# 07-PowerManagement.net
KiCad netlist of a schematic drawn in Altium Designer
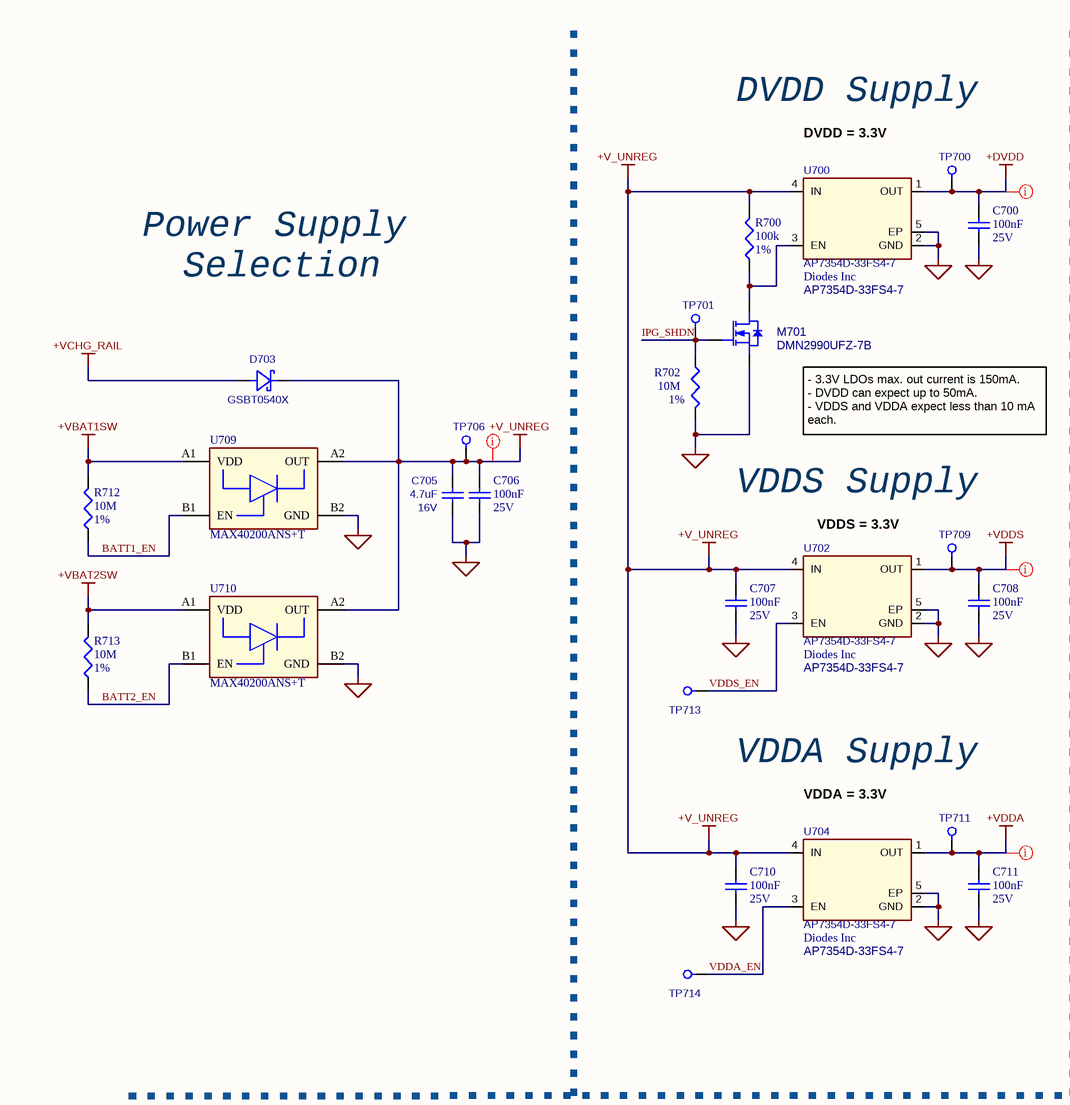
[diagram p0: 07-PowerManagement.SchDoc, left]
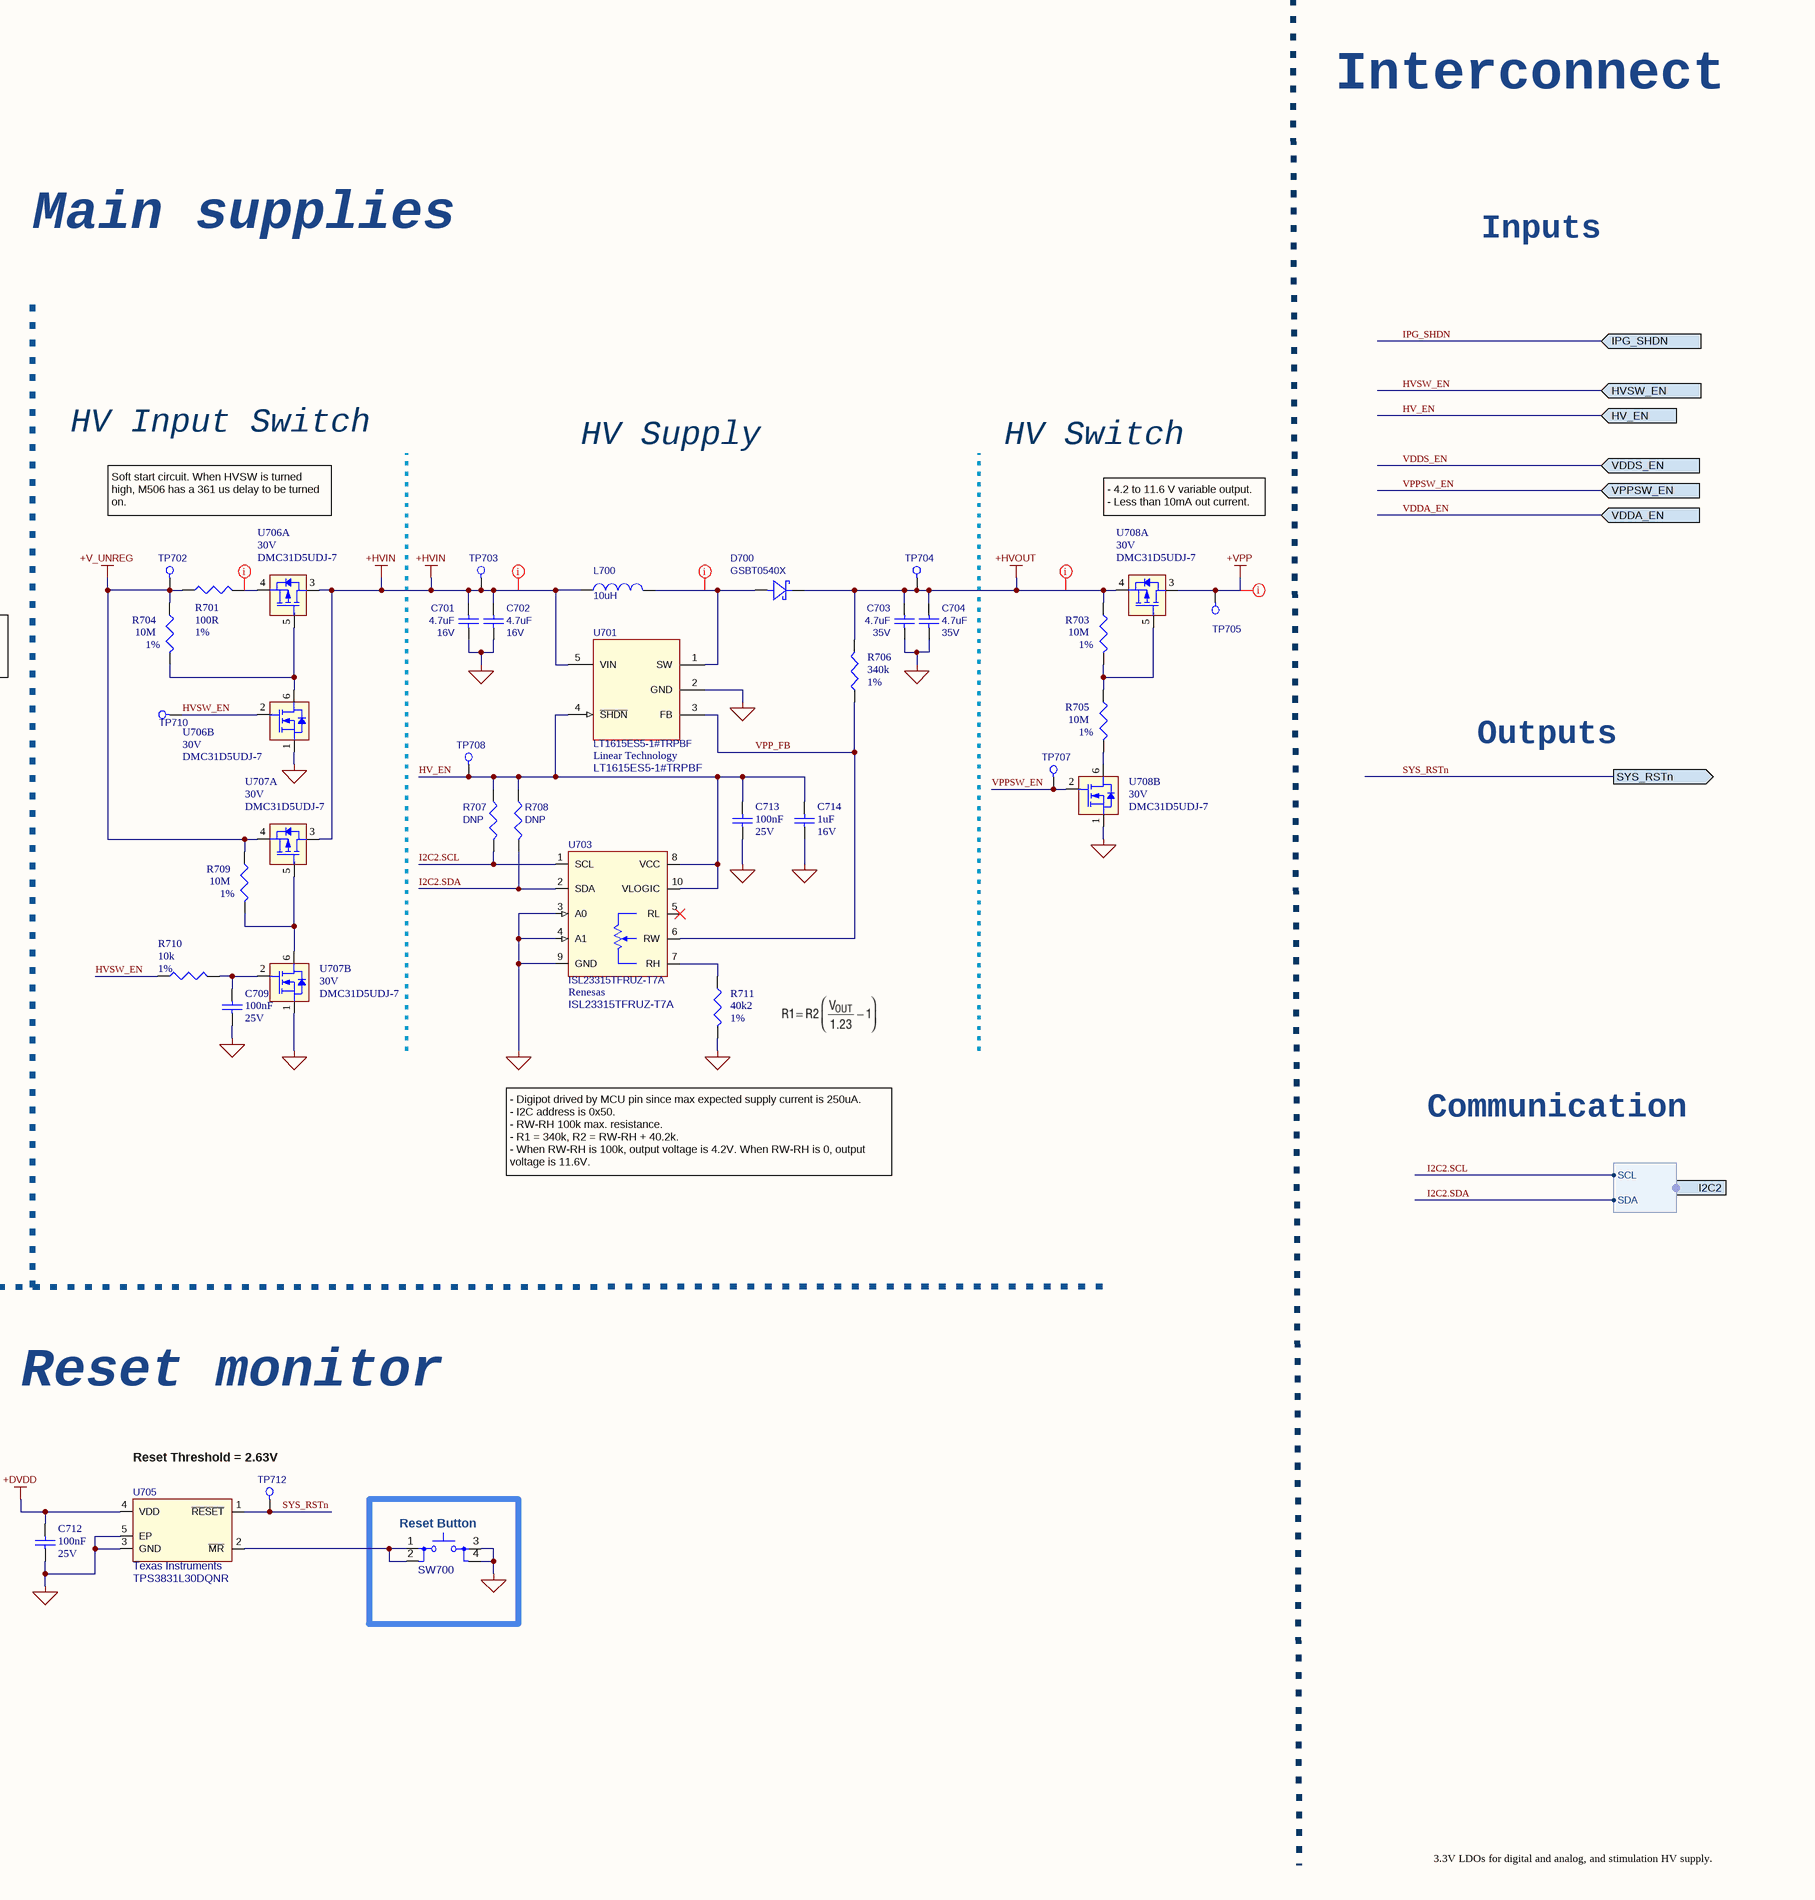
[diagram p1: 07-PowerManagement.SchDoc, right]

(export (version "E")
  (design (tool "Eeschema 10.0.6"))
  (components
    (comp (ref "C700")
      (value "100nF")
      (footprint "C0201_C")
      (fields
        (field (name "MANUFACTURER") "Murata")
        (field (name "MANUFACTURER PART NUMBER") "GRM033R61E104KE14J")
        (field (name "RATED DC VOLTAGE (URDC)") "25V")
      )
      (libsource (lib "MP-LIBRARY") (part "GRM033R61E104KE14J"))
    )
    (comp (ref "C701")
      (value "4.7uF")
      (footprint "CAP0603_REDUCED")
      (description "Capacitor, 4.7uF, X5R, 16V, 10%, 0603, Implant-grade")
      (fields
        (field (name "MANUFACTURER") "Murata")
        (field (name "RATING") "16V")
        (field (name "MANUFACTURER PART NUMBER") "GRM188R61C475KE11")
      )
      (libsource (lib "MP-LIBRARY") (part "GRM188R61C475KE11"))
    )
    (comp (ref "C702")
      (value "4.7uF")
      (footprint "CAP0603_REDUCED")
      (description "Capacitor, 4.7uF, X5R, 16V, 10%, 0603, Implant-grade")
      (fields
        (field (name "MANUFACTURER") "Murata")
        (field (name "RATING") "16V")
        (field (name "MANUFACTURER PART NUMBER") "GRM188R61C475KE11")
      )
      (libsource (lib "MP-LIBRARY") (part "GRM188R61C475KE11"))
    )
    (comp (ref "C703")
      (value "4.7uF")
      (footprint "CAP0805_REDUCED")
      (description "Capacitor, 4.7uF, X7S, 35V, 10%, 0805, Implant-grade")
      (fields
        (field (name "MANUFACTURER") "Murata")
        (field (name "RATING") "35V")
        (field (name "MANUFACTURER PART NUMBER") "GCM21BC7YA475KE36L")
      )
      (libsource (lib "MP-LIBRARY") (part "GCM21BC7YA475KE36L"))
    )
    (comp (ref "C704")
      (value "4.7uF")
      (footprint "CAP0805_REDUCED")
      (description "Capacitor, 4.7uF, X7S, 35V, 10%, 0805, Implant-grade")
      (fields
        (field (name "MANUFACTURER") "Murata")
        (field (name "RATING") "35V")
        (field (name "MANUFACTURER PART NUMBER") "GCM21BC7YA475KE36L")
      )
      (libsource (lib "MP-LIBRARY") (part "GCM21BC7YA475KE36L"))
    )
    (comp (ref "C705")
      (value "4.7uF")
      (footprint "CAP0603_REDUCED")
      (description "Capacitor, 4.7uF, X5R, 16V, 10%, 0603, Implant-grade")
      (fields
        (field (name "MANUFACTURER") "Murata")
        (field (name "RATING") "16V")
        (field (name "MANUFACTURER PART NUMBER") "GRM188R61C475KE11")
      )
      (libsource (lib "MP-LIBRARY") (part "GRM188R61C475KE11"))
    )
    (comp (ref "C706")
      (value "100nF")
      (footprint "C0201_C")
      (fields
        (field (name "MANUFACTURER") "Murata")
        (field (name "MANUFACTURER PART NUMBER") "GRM033R61E104KE14J")
        (field (name "RATED DC VOLTAGE (URDC)") "25V")
      )
      (libsource (lib "MP-LIBRARY") (part "GRM033R61E104KE14J"))
    )
    (comp (ref "C707")
      (value "100nF")
      (footprint "C0201_C")
      (fields
        (field (name "MANUFACTURER") "Murata")
        (field (name "MANUFACTURER PART NUMBER") "GRM033R61E104KE14J")
        (field (name "RATED DC VOLTAGE (URDC)") "25V")
      )
      (libsource (lib "MP-LIBRARY") (part "GRM033R61E104KE14J"))
    )
    (comp (ref "C708")
      (value "100nF")
      (footprint "C0201_C")
      (fields
        (field (name "MANUFACTURER") "Murata")
        (field (name "MANUFACTURER PART NUMBER") "GRM033R61E104KE14J")
        (field (name "RATED DC VOLTAGE (URDC)") "25V")
      )
      (libsource (lib "MP-LIBRARY") (part "GRM033R61E104KE14J"))
    )
    (comp (ref "C709")
      (value "100nF")
      (footprint "C0201_C")
      (fields
        (field (name "MANUFACTURER") "Murata")
        (field (name "MANUFACTURER PART NUMBER") "GRM033R61E104KE14J")
        (field (name "RATED DC VOLTAGE (URDC)") "25V")
      )
      (libsource (lib "MP-LIBRARY") (part "GRM033R61E104KE14J"))
    )
    (comp (ref "C710")
      (value "100nF")
      (footprint "C0201_C")
      (fields
        (field (name "MANUFACTURER") "Murata")
        (field (name "MANUFACTURER PART NUMBER") "GRM033R61E104KE14J")
        (field (name "RATED DC VOLTAGE (URDC)") "25V")
      )
      (libsource (lib "MP-LIBRARY") (part "GRM033R61E104KE14J"))
    )
    (comp (ref "C711")
      (value "100nF")
      (footprint "C0201_C")
      (fields
        (field (name "MANUFACTURER") "Murata")
        (field (name "MANUFACTURER PART NUMBER") "GRM033R61E104KE14J")
        (field (name "RATED DC VOLTAGE (URDC)") "25V")
      )
      (libsource (lib "MP-LIBRARY") (part "GRM033R61E104KE14J"))
    )
    (comp (ref "C712")
      (value "100nF")
      (footprint "C0201_C")
      (fields
        (field (name "MANUFACTURER") "Murata")
        (field (name "MANUFACTURER PART NUMBER") "GRM033R61E104KE14J")
        (field (name "RATED DC VOLTAGE (URDC)") "25V")
      )
      (libsource (lib "MP-LIBRARY") (part "GRM033R61E104KE14J"))
    )
    (comp (ref "C713")
      (value "100nF")
      (footprint "C0201_C")
      (fields
        (field (name "MANUFACTURER") "Murata")
        (field (name "MANUFACTURER PART NUMBER") "GRM033R61E104KE14J")
        (field (name "RATED DC VOLTAGE (URDC)") "25V")
      )
      (libsource (lib "MP-LIBRARY") (part "GRM033R61E104KE14J"))
    )
    (comp (ref "C714")
      (value "1uF")
      (footprint "C0201_C")
      (fields
        (field (name "MANUFACTURER") "Murata")
        (field (name "MANUFACTURER PART NUMBER") "GRM033R61C105ME15D")
        (field (name "RATED DC VOLTAGE (URDC)") "16V")
      )
      (libsource (lib "MP-LIBRARY") (part "GRM033R61C105ME15D"))
    )
    (comp (ref "D700")
      (value "GSBT0540X")
      (footprint "STM_SOD-523_R")
      (description "DIODE SCHOTTKY 40V 500MA SOD523")
      (fields (field (name "MANUFACTURER") "Good-Ark Semiconductor"))
      (libsource (lib "MP-LIBRARY") (part "GSBT0540X"))
    )
    (comp (ref "D703")
      (value "GSBT0540X")
      (footprint "STM_SOD-523_R")
      (description "DIODE SCHOTTKY 40V 500MA SOD523")
      (fields (field (name "MANUFACTURER") "Good-Ark Semiconductor"))
      (libsource (lib "MP-LIBRARY") (part "GSBT0540X"))
    )
    (comp (ref "L700")
      (value "10uH")
      (footprint "WURTH_74438323100_REDUCED")
      (description "Inductor, 10uH, 600mA, 20%, 1008")
      (fields (field (name "MANUFACTURER") "Wurth") (field (name "MANUFACTURER PART NUMBER") "74438323100"))
      (libsource (lib "MP-LIBRARY") (part "74438323100"))
    )
    (comp (ref "M701")
      (value "DMN2990UFZ-7B")
      (footprint "DIODESINC_X2-DFN0606-3")
      (description "MOSFET, N-Chan, 20V, 170mA, DFN0606")
      (fields (field (name "MANUFACTURER") "Diodes Inc"))
      (libsource (lib "MP-LIBRARY") (part "DMN2990UFZ-7B"))
    )
    (comp (ref "R700")
      (value "100k")
      (footprint "R0201_C")
      (fields
        (field (name "MANUFACTURER") "Vishay")
        (field (name "MANUFACTURER PART NUMBER") "CRCW0201100KFNED")
        (field (name "TOLERANCE") "1%")
        (field (name "POWER") "50mW")
      )
      (libsource (lib "MP-LIBRARY") (part "CRCW0201100KFNED"))
    )
    (comp (ref "R701")
      (value "100R")
      (footprint "R0201_C")
      (fields
        (field (name "MANUFACTURER") "Vishay")
        (field (name "MANUFACTURER PART NUMBER") "CRCW0201100RFNED")
        (field (name "TOLERANCE") "1%")
        (field (name "POWER") "50mW")
      )
      (libsource (lib "MP-LIBRARY") (part "CRCW0201100RFNED"))
    )
    (comp (ref "R702")
      (value "10M")
      (footprint "R0201_C")
      (fields
        (field (name "MANUFACTURER") "Vishay Draloric")
        (field (name "MANUFACTURER PART NUMBER") "CRCW020110M0FNED")
        (field (name "TOLERANCE") "1%")
        (field (name "POWER") "50mW")
      )
      (libsource (lib "MP-LIBRARY") (part "CRCW020110M0FNED"))
    )
    (comp (ref "R703")
      (value "10M")
      (footprint "R0201_C")
      (fields
        (field (name "MANUFACTURER") "Vishay Draloric")
        (field (name "MANUFACTURER PART NUMBER") "CRCW020110M0FNED")
        (field (name "TOLERANCE") "1%")
        (field (name "POWER") "50mW")
      )
      (libsource (lib "MP-LIBRARY") (part "CRCW020110M0FNED"))
    )
    (comp (ref "R704")
      (value "10M")
      (footprint "R0201_C")
      (fields
        (field (name "MANUFACTURER") "Vishay Draloric")
        (field (name "MANUFACTURER PART NUMBER") "CRCW020110M0FNED")
        (field (name "TOLERANCE") "1%")
        (field (name "POWER") "50mW")
      )
      (libsource (lib "MP-LIBRARY") (part "CRCW020110M0FNED"))
    )
    (comp (ref "R705")
      (value "10M")
      (footprint "R0201_C")
      (fields
        (field (name "MANUFACTURER") "Vishay Draloric")
        (field (name "MANUFACTURER PART NUMBER") "CRCW020110M0FNED")
        (field (name "TOLERANCE") "1%")
        (field (name "POWER") "50mW")
      )
      (libsource (lib "MP-LIBRARY") (part "CRCW020110M0FNED"))
    )
    (comp (ref "R706")
      (value "340k")
      (footprint "R0201_C")
      (fields
        (field (name "MANUFACTURER") "Vishay")
        (field (name "MANUFACTURER PART NUMBER") "CRCW0201340KFKED")
        (field (name "TOLERANCE") "1%")
        (field (name "POWER") "50mW")
      )
      (libsource (lib "MP-LIBRARY") (part "CRCW0201340KFKED"))
    )
    (comp (ref "R707")
      (value "DNP")
      (footprint "RES0402_REDUCED")
      (description "Resistor, DNP, 0402")
      (libsource (lib "MP-LIBRARY") (part "RES_DNP_0402"))
    )
    (comp (ref "R708")
      (value "DNP")
      (footprint "RES0402_REDUCED")
      (description "Resistor, DNP, 0402")
      (libsource (lib "MP-LIBRARY") (part "RES_DNP_0402"))
    )
    (comp (ref "R709")
      (value "10M")
      (footprint "R0201_C")
      (fields
        (field (name "MANUFACTURER") "Vishay Draloric")
        (field (name "MANUFACTURER PART NUMBER") "CRCW020110M0FNED")
        (field (name "TOLERANCE") "1%")
        (field (name "POWER") "50mW")
      )
      (libsource (lib "MP-LIBRARY") (part "CRCW020110M0FNED"))
    )
    (comp (ref "R710")
      (value "10k")
      (footprint "R0201_C")
      (fields
        (field (name "MANUFACTURER") "Vishay")
        (field (name "MANUFACTURER PART NUMBER") "CRCW020110K0FNED")
        (field (name "TOLERANCE") "1%")
        (field (name "POWER") "50mW")
      )
      (libsource (lib "MP-LIBRARY") (part "CRCW020110K0FNED"))
    )
    (comp (ref "R711")
      (value "40k2")
      (footprint "R0201_C")
      (fields
        (field (name "MANUFACTURER") "Vishay")
        (field (name "MANUFACTURER PART NUMBER") "CRCW020140K2FNED")
        (field (name "TOLERANCE") "1%")
        (field (name "POWER") "50mW")
      )
      (libsource (lib "MP-LIBRARY") (part "CRCW020140K2FNED"))
    )
    (comp (ref "R712")
      (value "10M")
      (footprint "R0201_C")
      (fields
        (field (name "MANUFACTURER") "Vishay Draloric")
        (field (name "MANUFACTURER PART NUMBER") "CRCW020110M0FNED")
        (field (name "TOLERANCE") "1%")
        (field (name "POWER") "50mW")
      )
      (libsource (lib "MP-LIBRARY") (part "CRCW020110M0FNED"))
    )
    (comp (ref "R713")
      (value "10M")
      (footprint "R0201_C")
      (fields
        (field (name "MANUFACTURER") "Vishay Draloric")
        (field (name "MANUFACTURER PART NUMBER") "CRCW020110M0FNED")
        (field (name "TOLERANCE") "1%")
        (field (name "POWER") "50mW")
      )
      (libsource (lib "MP-LIBRARY") (part "CRCW020110M0FNED"))
    )
    (comp (ref "SW700")
      (value "PTS647SN50SMTR2LFS")
      (footprint "CK_PTS647")
      (description "Pushbutton, NO-MOM, 12V, 0.05A, SMT")
      (fields (field (name "MANUFACTURER") "C&K"))
      (libsource (lib "MP-LIBRARY") (part "PTS647SN50SMTR2LFS"))
    )
    (comp (ref "TP700")
      (value "Test Point")
      (footprint "testpad_0.9mm")
      (description "Test pad, 0.90mm circular pad")
      (libsource (lib "MP-LIBRARY") (part "Test Point"))
    )
    (comp (ref "TP701")
      (value "Test Point")
      (footprint "testpad_0.9mm")
      (description "Test pad, 0.90mm circular pad")
      (libsource (lib "MP-LIBRARY") (part "Test Point"))
    )
    (comp (ref "TP702")
      (value "Test Point")
      (footprint "testpad_0.9mm")
      (description "Test pad, 0.90mm circular pad")
      (libsource (lib "MP-LIBRARY") (part "Test Point"))
    )
    (comp (ref "TP703")
      (value "Test Point")
      (footprint "testpad_0.9mm")
      (description "Test pad, 0.90mm circular pad")
      (libsource (lib "MP-LIBRARY") (part "Test Point"))
    )
    (comp (ref "TP704")
      (value "Test Point")
      (footprint "testpad_0.9mm")
      (description "Test pad, 0.90mm circular pad")
      (libsource (lib "MP-LIBRARY") (part "Test Point"))
    )
    (comp (ref "TP705")
      (value "Test Point")
      (footprint "testpad_0.9mm")
      (description "Test pad, 0.90mm circular pad")
      (libsource (lib "MP-LIBRARY") (part "Test Point"))
    )
    (comp (ref "TP706")
      (value "Test Point")
      (footprint "testpad_0.9mm")
      (description "Test pad, 0.90mm circular pad")
      (libsource (lib "MP-LIBRARY") (part "Test Point"))
    )
    (comp (ref "TP707")
      (value "Test Point")
      (footprint "testpad_0.9mm")
      (description "Test pad, 0.90mm circular pad")
      (libsource (lib "MP-LIBRARY") (part "Test Point"))
    )
    (comp (ref "TP708")
      (value "Test Point")
      (footprint "testpad_0.9mm")
      (description "Test pad, 0.90mm circular pad")
      (libsource (lib "MP-LIBRARY") (part "Test Point"))
    )
    (comp (ref "TP709")
      (value "Test Point")
      (footprint "testpad_0.9mm")
      (description "Test pad, 0.90mm circular pad")
      (libsource (lib "MP-LIBRARY") (part "Test Point"))
    )
    (comp (ref "TP710")
      (value "Test Point")
      (footprint "testpad_0.9mm")
      (description "Test pad, 0.90mm circular pad")
      (libsource (lib "MP-LIBRARY") (part "Test Point"))
    )
    (comp (ref "TP711")
      (value "Test Point")
      (footprint "testpad_0.9mm")
      (description "Test pad, 0.90mm circular pad")
      (libsource (lib "MP-LIBRARY") (part "Test Point"))
    )
    (comp (ref "TP712")
      (value "Test Point")
      (footprint "testpad_0.9mm")
      (description "Test pad, 0.90mm circular pad")
      (libsource (lib "MP-LIBRARY") (part "Test Point"))
    )
    (comp (ref "TP713")
      (value "Test Point")
      (footprint "testpad_0.9mm")
      (description "Test pad, 0.90mm circular pad")
      (libsource (lib "MP-LIBRARY") (part "Test Point"))
    )
    (comp (ref "TP714")
      (value "Test Point")
      (footprint "testpad_0.9mm")
      (description "Test pad, 0.90mm circular pad")
      (libsource (lib "MP-LIBRARY") (part "Test Point"))
    )
    (comp (ref "U700")
      (value "AP7354D-33FS4-7")
      (footprint "X2-DFN1010-4 (Type B)")
      (description "LDO Regulator, 3.3V, Shutdown, DFN1010-4")
      (fields (field (name "MANUFACTURER") "Diodes Inc") (field (name "ALTIUM_VALUE") "AP7354D-33FS4-7"))
      (libsource (lib "MP-LIBRARY") (part "AP7354D-33FS4-7"))
    )
    (comp (ref "U701")
      (value "LT1615ES5-1#TRPBF")
      (footprint "LT_S5_L")
      (description "Boost, SEPIC Switching Regulator IC Positive Adjustable 1.23V 1 Output 75mA (Switch) SOT-23-5")
      (fields
        (field (name "MANUFACTURER") "Linear Technology")
        (field (name "ALTIUM_VALUE") "LT1615ES5-1#TRPBF")
      )
      (libsource (lib "MP-LIBRARY") (part "LT1615ES5-1#TRPBF"))
    )
    (comp (ref "U702")
      (value "AP7354D-33FS4-7")
      (footprint "X2-DFN1010-4 (Type B)")
      (description "LDO Regulator, 3.3V, Shutdown, DFN1010-4")
      (fields (field (name "MANUFACTURER") "Diodes Inc") (field (name "ALTIUM_VALUE") "AP7354D-33FS4-7"))
      (libsource (lib "MP-LIBRARY") (part "AP7354D-33FS4-7"))
    )
    (comp (ref "U703")
      (value "ISL23315TFRUZ-T7A")
      (footprint "RENESAS_L10.2.1X1.6A_UTQFN10")
      (description "Digital potentiometer, 256 taps, 100k, I2C, QFN-10")
      (fields (field (name "MANUFACTURER") "Renesas") (field (name "ALTIUM_VALUE") "ISL23315TFRUZ-T7A"))
      (libsource (lib "MP-LIBRARY") (part "ISL23315TFRUZ-T7A"))
    )
    (comp (ref "U704")
      (value "AP7354D-33FS4-7")
      (footprint "X2-DFN1010-4 (Type B)")
      (description "LDO Regulator, 3.3V, Shutdown, DFN1010-4")
      (fields (field (name "MANUFACTURER") "Diodes Inc") (field (name "ALTIUM_VALUE") "AP7354D-33FS4-7"))
      (libsource (lib "MP-LIBRARY") (part "AP7354D-33FS4-7"))
    )
    (comp (ref "U705")
      (value "TPS3831L30DQNR")
      (footprint "TI_X2SON_DQN0004A")
      (description "Reset Monitor, 2.63V, Active low, X2SON")
      (fields (field (name "MANUFACTURER") "Texas Instruments"))
      (libsource (lib "MP-LIBRARY") (part "TPS3831L30DQNR"))
    )
    (comp (ref "U706")
      (value "DMC31D5UDJ-7")
      (footprint "DIODESINC_SOT-963-6")
      (description "MOSFET N/P-CH 30V 0.22A SOT963")
      (fields (field (name "MANUFACTURER") "Diodes inc.") (field (name "VDS(MAX)") "30V"))
      (libsource (lib "MP-LIBRARY") (part "DMC31D5UDJ-7"))
    )
    (comp (ref "U707")
      (value "DMC31D5UDJ-7")
      (footprint "DIODESINC_SOT-963-6")
      (description "MOSFET N/P-CH 30V 0.22A SOT963")
      (fields (field (name "MANUFACTURER") "Diodes inc.") (field (name "VDS(MAX)") "30V"))
      (libsource (lib "MP-LIBRARY") (part "DMC31D5UDJ-7"))
    )
    (comp (ref "U708")
      (value "DMC31D5UDJ-7")
      (footprint "DIODESINC_SOT-963-6")
      (description "MOSFET N/P-CH 30V 0.22A SOT963")
      (fields (field (name "MANUFACTURER") "Diodes inc.") (field (name "VDS(MAX)") "30V"))
      (libsource (lib "MP-LIBRARY") (part "DMC31D5UDJ-7"))
    )
    (comp (ref "U709")
      (value "MAX40200ANS+T")
      (footprint "BGA4N35P2X2_72X72X50N")
      (description "OR Controller Source Selector Switch P-Channel 1:1 4-WLP (0.73x0.73)")
      (fields (field (name "MANUFACTURER") "Maxim Integrated"))
      (libsource (lib "MP-LIBRARY") (part "MAX40200ANS+T"))
    )
    (comp (ref "U710")
      (value "MAX40200ANS+T")
      (footprint "BGA4N35P2X2_72X72X50N")
      (description "OR Controller Source Selector Switch P-Channel 1:1 4-WLP (0.73x0.73)")
      (fields (field (name "MANUFACTURER") "Maxim Integrated"))
      (libsource (lib "MP-LIBRARY") (part "MAX40200ANS+T"))
    )
  )
  (nets
    (net (code "2") (name "+DVDD") (class "Default")
      (node (ref "C700") (pin "2") (pinfunction "2_2") (pintype "passive"))
      (node (ref "C712") (pin "2") (pinfunction "2_2") (pintype "passive"))
      (node (ref "TP700") (pin "1") (pinfunction "1_1") (pintype "passive"))
      (node (ref "U700") (pin "1") (pinfunction "OUT_1") (pintype "passive"))
      (node (ref "U705") (pin "4") (pinfunction "VDD_4") (pintype "passive"))
    )
    (net (code "3") (name "+HVIN") (class "Default")
      (node (ref "C701") (pin "1") (pinfunction "1_1") (pintype "passive"))
      (node (ref "C702") (pin "1") (pinfunction "1_1") (pintype "passive"))
      (node (ref "L700") (pin "1") (pinfunction "1_1") (pintype "passive"))
      (node (ref "TP703") (pin "1") (pinfunction "1_1") (pintype "passive"))
      (node (ref "U701") (pin "5") (pinfunction "VIN_5") (pintype "power_in"))
      (node (ref "U706") (pin "3") (pinfunction "3_3") (pintype "passive"))
      (node (ref "U707") (pin "3") (pinfunction "3_3") (pintype "passive"))
    )
    (net (code "4") (name "+HVOUT") (class "Default")
      (node (ref "C703") (pin "1") (pinfunction "1_1") (pintype "passive"))
      (node (ref "C704") (pin "1") (pinfunction "1_1") (pintype "passive"))
      (node (ref "D700") (pin "1") (pinfunction "1_1") (pintype "passive"))
      (node (ref "R703") (pin "1") (pinfunction "1_1") (pintype "passive"))
      (node (ref "R706") (pin "2") (pinfunction "2_2") (pintype "passive"))
      (node (ref "TP704") (pin "1") (pinfunction "1_1") (pintype "passive"))
      (node (ref "U708") (pin "4") (pinfunction "4_4") (pintype "passive"))
    )
    (net (code "5") (name "+VBAT1SW") (class "Default")
      (node (ref "R712") (pin "2") (pinfunction "2_2") (pintype "passive"))
      (node (ref "U709") (pin "A1") (pinfunction "VDD_A1") (pintype "passive"))
    )
    (net (code "6") (name "+VBAT2SW") (class "Default")
      (node (ref "R713") (pin "2") (pinfunction "2_2") (pintype "passive"))
      (node (ref "U710") (pin "A1") (pinfunction "VDD_A1") (pintype "passive"))
    )
    (net (code "7") (name "+VCHG_RAIL") (class "Default")
      (node (ref "D703") (pin "2") (pinfunction "2_2") (pintype "passive"))
    )
    (net (code "8") (name "+VDDA") (class "Default")
      (node (ref "C711") (pin "2") (pinfunction "2_2") (pintype "passive"))
      (node (ref "TP711") (pin "1") (pinfunction "1_1") (pintype "passive"))
      (node (ref "U704") (pin "1") (pinfunction "OUT_1") (pintype "passive"))
    )
    (net (code "9") (name "+VDDS") (class "Default")
      (node (ref "C708") (pin "2") (pinfunction "2_2") (pintype "passive"))
      (node (ref "TP709") (pin "1") (pinfunction "1_1") (pintype "passive"))
      (node (ref "U702") (pin "1") (pinfunction "OUT_1") (pintype "passive"))
    )
    (net (code "10") (name "+VPP") (class "Default")
      (node (ref "TP705") (pin "1") (pinfunction "1_1") (pintype "passive"))
      (node (ref "U708") (pin "3") (pinfunction "3_3") (pintype "passive"))
    )
    (net (code "11") (name "+V_UNREG") (class "Default")
      (node (ref "C705") (pin "1") (pinfunction "1_1") (pintype "passive"))
      (node (ref "C706") (pin "2") (pinfunction "2_2") (pintype "passive"))
      (node (ref "C707") (pin "2") (pinfunction "2_2") (pintype "passive"))
      (node (ref "C710") (pin "2") (pinfunction "2_2") (pintype "passive"))
      (node (ref "D703") (pin "1") (pinfunction "1_1") (pintype "passive"))
      (node (ref "R700") (pin "2") (pinfunction "2_2") (pintype "passive"))
      (node (ref "R701") (pin "1") (pinfunction "1_1") (pintype "passive"))
      (node (ref "R704") (pin "1") (pinfunction "1_1") (pintype "passive"))
      (node (ref "R709") (pin "1") (pinfunction "1_1") (pintype "passive"))
      (node (ref "TP702") (pin "1") (pinfunction "1_1") (pintype "passive"))
      (node (ref "TP706") (pin "1") (pinfunction "1_1") (pintype "passive"))
      (node (ref "U700") (pin "4") (pinfunction "IN_4") (pintype "passive"))
      (node (ref "U702") (pin "4") (pinfunction "IN_4") (pintype "passive"))
      (node (ref "U704") (pin "4") (pinfunction "IN_4") (pintype "passive"))
      (node (ref "U707") (pin "4") (pinfunction "4_4") (pintype "passive"))
      (node (ref "U709") (pin "A2") (pinfunction "OUT_A2") (pintype "passive"))
      (node (ref "U710") (pin "A2") (pinfunction "OUT_A2") (pintype "passive"))
    )
    (net (code "12") (name "/BATT1_EN") (class "Default")
      (node (ref "R712") (pin "1") (pinfunction "1_1") (pintype "passive"))
      (node (ref "U709") (pin "B1") (pinfunction "EN_B1") (pintype "passive"))
    )
    (net (code "13") (name "/BATT2_EN") (class "Default")
      (node (ref "R713") (pin "1") (pinfunction "1_1") (pintype "passive"))
      (node (ref "U710") (pin "B1") (pinfunction "EN_B1") (pintype "passive"))
    )
    (net (code "14") (name "/HVSW_EN") (class "Default")
      (node (ref "R710") (pin "1") (pinfunction "1_1") (pintype "passive"))
      (node (ref "TP710") (pin "1") (pinfunction "1_1") (pintype "passive"))
      (node (ref "U706") (pin "2") (pinfunction "2_2") (pintype "passive"))
    )
    (net (code "15") (name "/HV_EN") (class "Default")
      (node (ref "C713") (pin "2") (pinfunction "2_2") (pintype "passive"))
      (node (ref "C714") (pin "2") (pinfunction "2_2") (pintype "passive"))
      (node (ref "R707") (pin "1") (pinfunction "1_1") (pintype "passive"))
      (node (ref "R708") (pin "1") (pinfunction "1_1") (pintype "passive"))
      (node (ref "TP708") (pin "1") (pinfunction "1_1") (pintype "passive"))
      (node (ref "U701") (pin "4") (pinfunction "~{SHDN}_4") (pintype "input"))
      (node (ref "U703") (pin "10") (pinfunction "VLOGIC_10") (pintype "passive"))
      (node (ref "U703") (pin "8") (pinfunction "VCC_8") (pintype "passive"))
    )
    (net (code "16") (name "/I2C2.SCL") (class "Default")
      (node (ref "R707") (pin "2") (pinfunction "2_2") (pintype "passive"))
      (node (ref "U703") (pin "1") (pinfunction "SCL_1") (pintype "passive"))
    )
    (net (code "17") (name "/I2C2.SDA") (class "Default")
      (node (ref "R708") (pin "2") (pinfunction "2_2") (pintype "passive"))
      (node (ref "U703") (pin "2") (pinfunction "SDA_2") (pintype "passive"))
    )
    (net (code "18") (name "/IPG_SHDN") (class "Default")
      (node (ref "M701") (pin "1") (pinfunction "G_1") (pintype "passive"))
      (node (ref "R702") (pin "1") (pinfunction "1_1") (pintype "passive"))
      (node (ref "TP701") (pin "1") (pinfunction "1_1") (pintype "passive"))
    )
    (net (code "19") (name "/SYS_RSTn") (class "Default")
      (node (ref "TP712") (pin "1") (pinfunction "1_1") (pintype "passive"))
      (node (ref "U705") (pin "1") (pinfunction "~{RESET}_1") (pintype "passive"))
    )
    (net (code "20") (name "/VDDA_EN") (class "Default")
      (node (ref "TP714") (pin "1") (pinfunction "1_1") (pintype "passive"))
      (node (ref "U704") (pin "3") (pinfunction "EN_3") (pintype "passive"))
    )
    (net (code "21") (name "/VDDS_EN") (class "Default")
      (node (ref "TP713") (pin "1") (pinfunction "1_1") (pintype "passive"))
      (node (ref "U702") (pin "3") (pinfunction "EN_3") (pintype "passive"))
    )
    (net (code "22") (name "/VPPSW_EN") (class "Default")
      (node (ref "TP707") (pin "1") (pinfunction "1_1") (pintype "passive"))
      (node (ref "U708") (pin "2") (pinfunction "2_2") (pintype "passive"))
    )
    (net (code "23") (name "/VPP_FB") (class "Default")
      (node (ref "R706") (pin "1") (pinfunction "1_1") (pintype "passive"))
      (node (ref "U701") (pin "3") (pinfunction "FB_3") (pintype "passive"))
      (node (ref "U703") (pin "6") (pinfunction "RW_6") (pintype "passive"))
    )
    (net (code "25") (name "GND") (class "Default")
      (node (ref "C700") (pin "1") (pinfunction "1_1") (pintype "passive"))
      (node (ref "C701") (pin "2") (pinfunction "2_2") (pintype "passive"))
      (node (ref "C702") (pin "2") (pinfunction "2_2") (pintype "passive"))
      (node (ref "C703") (pin "2") (pinfunction "2_2") (pintype "passive"))
      (node (ref "C704") (pin "2") (pinfunction "2_2") (pintype "passive"))
      (node (ref "C705") (pin "2") (pinfunction "2_2") (pintype "passive"))
      (node (ref "C706") (pin "1") (pinfunction "1_1") (pintype "passive"))
      (node (ref "C707") (pin "1") (pinfunction "1_1") (pintype "passive"))
      (node (ref "C708") (pin "1") (pinfunction "1_1") (pintype "passive"))
      (node (ref "C709") (pin "1") (pinfunction "1_1") (pintype "passive"))
      (node (ref "C710") (pin "1") (pinfunction "1_1") (pintype "passive"))
      (node (ref "C711") (pin "1") (pinfunction "1_1") (pintype "passive"))
      (node (ref "C712") (pin "1") (pinfunction "1_1") (pintype "passive"))
      (node (ref "C713") (pin "1") (pinfunction "1_1") (pintype "passive"))
      (node (ref "C714") (pin "1") (pinfunction "1_1") (pintype "passive"))
      (node (ref "M701") (pin "2") (pinfunction "S_2") (pintype "passive"))
      (node (ref "R702") (pin "2") (pinfunction "2_2") (pintype "passive"))
      (node (ref "R711") (pin "2") (pinfunction "2_2") (pintype "passive"))
      (node (ref "SW700") (pin "3") (pinfunction "3_3") (pintype "passive"))
      (node (ref "SW700") (pin "4") (pinfunction "4_4") (pintype "passive"))
      (node (ref "U700") (pin "2") (pinfunction "GND_2") (pintype "power_in"))
      (node (ref "U700") (pin "5") (pinfunction "EP_5") (pintype "passive"))
      (node (ref "U701") (pin "2") (pinfunction "GND_2") (pintype "power_in"))
      (node (ref "U702") (pin "2") (pinfunction "GND_2") (pintype "power_in"))
      (node (ref "U702") (pin "5") (pinfunction "EP_5") (pintype "passive"))
      (node (ref "U703") (pin "3") (pinfunction "A0_3") (pintype "input"))
      (node (ref "U703") (pin "4") (pinfunction "A1_4") (pintype "input"))
      (node (ref "U703") (pin "9") (pinfunction "GND_9") (pintype "power_in"))
      (node (ref "U704") (pin "2") (pinfunction "GND_2") (pintype "power_in"))
      (node (ref "U704") (pin "5") (pinfunction "EP_5") (pintype "passive"))
      (node (ref "U705") (pin "3") (pinfunction "GND_3") (pintype "passive"))
      (node (ref "U705") (pin "5") (pinfunction "EP_5") (pintype "passive"))
      (node (ref "U706") (pin "1") (pinfunction "1_1") (pintype "passive"))
      (node (ref "U707") (pin "1") (pinfunction "1_1") (pintype "passive"))
      (node (ref "U708") (pin "1") (pinfunction "1_1") (pintype "passive"))
      (node (ref "U709") (pin "B2") (pinfunction "GND_B2") (pintype "passive"))
      (node (ref "U710") (pin "B2") (pinfunction "GND_B2") (pintype "passive"))
    )
    (net (code "26") (name "Net-(C709-Pad2)") (class "Default")
      (node (ref "C709") (pin "2") (pinfunction "2_2") (pintype "passive"))
      (node (ref "R710") (pin "2") (pinfunction "2_2") (pintype "passive"))
      (node (ref "U707") (pin "2") (pinfunction "2_2") (pintype "passive"))
    )
    (net (code "27") (name "Net-(M701-D)") (class "Default")
      (node (ref "M701") (pin "3") (pinfunction "D_3") (pintype "passive"))
      (node (ref "R700") (pin "1") (pinfunction "1_1") (pintype "passive"))
      (node (ref "U700") (pin "3") (pinfunction "EN_3") (pintype "passive"))
    )
    (net (code "28") (name "Net-(R701-Pad2)") (class "Default")
      (node (ref "R701") (pin "2") (pinfunction "2_2") (pintype "passive"))
      (node (ref "U706") (pin "4") (pinfunction "4_4") (pintype "passive"))
    )
    (net (code "29") (name "Net-(R703-Pad2)") (class "Default")
      (node (ref "R703") (pin "2") (pinfunction "2_2") (pintype "passive"))
      (node (ref "R705") (pin "1") (pinfunction "1_1") (pintype "passive"))
      (node (ref "U708") (pin "5") (pinfunction "5_5") (pintype "passive"))
    )
    (net (code "30") (name "Net-(R704-Pad2)") (class "Default")
      (node (ref "R704") (pin "2") (pinfunction "2_2") (pintype "passive"))
      (node (ref "U706") (pin "5") (pinfunction "5_5") (pintype "passive"))
      (node (ref "U706") (pin "6") (pinfunction "6_6") (pintype "passive"))
    )
    (net (code "31") (name "Net-(R705-Pad2)") (class "Default")
      (node (ref "R705") (pin "2") (pinfunction "2_2") (pintype "passive"))
      (node (ref "U708") (pin "6") (pinfunction "6_6") (pintype "passive"))
    )
    (net (code "32") (name "Net-(R709-Pad2)") (class "Default")
      (node (ref "R709") (pin "2") (pinfunction "2_2") (pintype "passive"))
      (node (ref "U707") (pin "5") (pinfunction "5_5") (pintype "passive"))
      (node (ref "U707") (pin "6") (pinfunction "6_6") (pintype "passive"))
    )
    (net (code "33") (name "Net-(U701-SW)") (class "Default")
      (node (ref "D700") (pin "2") (pinfunction "2_2") (pintype "passive"))
      (node (ref "L700") (pin "2") (pinfunction "2_2") (pintype "passive"))
      (node (ref "U701") (pin "1") (pinfunction "SW_1") (pintype "passive"))
    )
    (net (code "34") (name "Net-(U703-RH)") (class "Default")
      (node (ref "R711") (pin "1") (pinfunction "1_1") (pintype "passive"))
      (node (ref "U703") (pin "7") (pinfunction "RH_7") (pintype "passive"))
    )
    (net (code "35") (name "Net-(U705-~{MR})") (class "Default")
      (node (ref "SW700") (pin "1") (pinfunction "1_1") (pintype "passive"))
      (node (ref "SW700") (pin "2") (pinfunction "2_2") (pintype "passive"))
      (node (ref "U705") (pin "2") (pinfunction "~{MR}_2") (pintype "passive"))
    )
    (net (code "36") (name "unconnected-(U703-RL-Pad5)") (class "Default")
      (node (ref "U703") (pin "5") (pinfunction "RL_5") (pintype "passive+no_connect"))
    )
  )
)
